# SCH_Auto-tune-FM-reciever_2024-02-23.net
KiCad netlist of a schematic drawn in EasyEDA
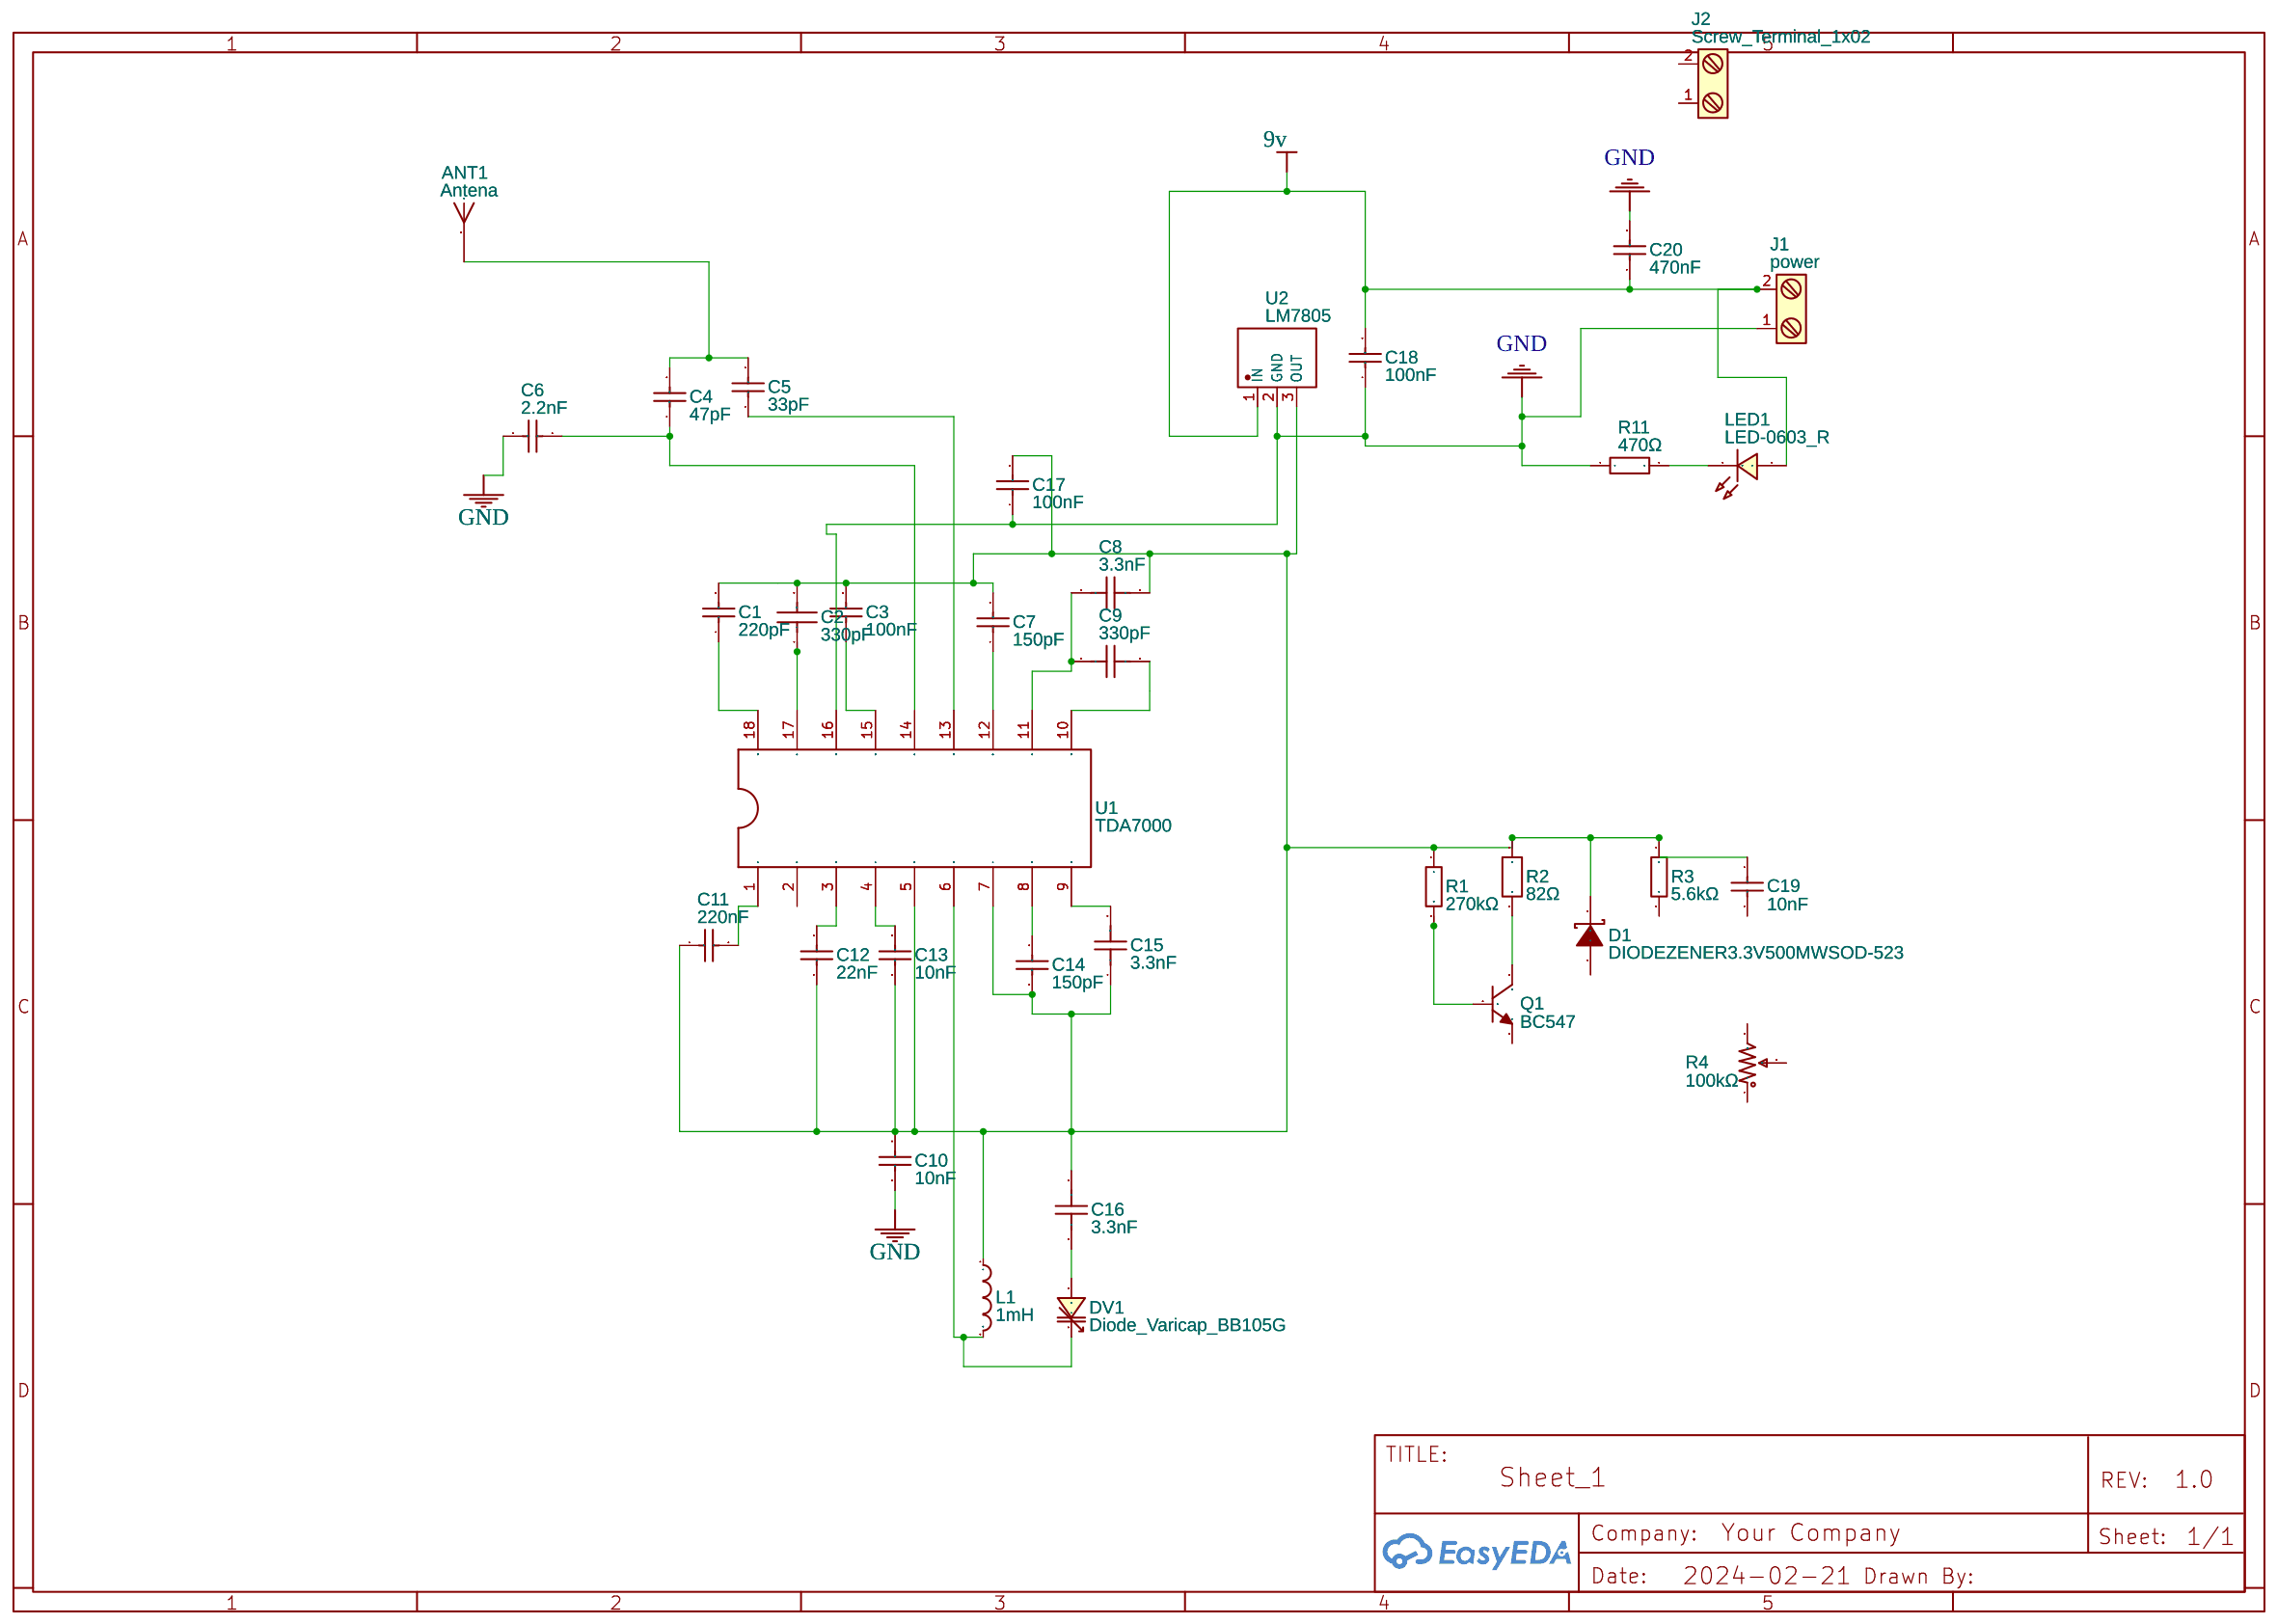
[diagram p0: schematic sheet]

(export (version "E")
  (design (tool "Eeschema 10.0.6"))
  (components
    (comp (ref "ANT1")
      (value "Antena")
      (fields (field (name "Manufacturer Part") "?"))
      (libsource (lib "") (part "Antena"))
    )
    (comp (ref "C1")
      (value "220pF")
      (fields
        (field (name "Manufacturer Part") "CL10B221KB8NNNC")
        (field (name "Manufacturer") "SAMSUNG(三星)")
      )
      (libsource (lib "") (part "CL10B221KB8NNNC"))
    )
    (comp (ref "C2")
      (value "330pF")
      (fields
        (field (name "Manufacturer Part") "CL05C331JB5NNNC")
        (field (name "Manufacturer") "SAMSUNG(三星)")
      )
      (libsource (lib "") (part "CL05C331JB5NNNC"))
    )
    (comp (ref "C3")
      (value "100nF")
      (fields
        (field (name "Manufacturer Part") "CL31B104KBCNNNC")
        (field (name "Manufacturer") "SAMSUNG(三星)")
      )
      (libsource (lib "") (part "CL31B104KBCNNNC"))
    )
    (comp (ref "C4")
      (value "47pF")
      (fields
        (field (name "Manufacturer Part") "CL10C470JB8NNNC")
        (field (name "Manufacturer") "SAMSUNG(三星)")
      )
      (libsource (lib "") (part "CL10C470JB8NNNC"))
    )
    (comp (ref "C5")
      (value "33pF")
      (fields
        (field (name "Manufacturer Part") "CL10C330JB8NNNC")
        (field (name "Manufacturer") "SAMSUNG(三星)")
      )
      (libsource (lib "") (part "CL10C330JB8NNNC"))
    )
    (comp (ref "C6")
      (value "2.2nF")
      (fields
        (field (name "Manufacturer Part") "CL21B222KBANNNC")
        (field (name "Manufacturer") "SAMSUNG(三星)")
      )
      (libsource (lib "") (part "CL21B222KBANNNC"))
    )
    (comp (ref "C7")
      (value "150pF")
      (fields
        (field (name "Manufacturer Part") "CL10C151JB8NNNC")
        (field (name "Manufacturer") "SAMSUNG(三星)")
      )
      (libsource (lib "") (part "CL10C151JB8NNNC"))
    )
    (comp (ref "C8")
      (value "3.3nF")
      (fields
        (field (name "Manufacturer Part") "CL05B332KB5NNNC")
        (field (name "Manufacturer") "SAMSUNG(三星)")
      )
      (libsource (lib "") (part "CL05B332KB5NNNC"))
    )
    (comp (ref "C9")
      (value "330pF")
      (fields
        (field (name "Manufacturer Part") "CL10B331KB8NNNC")
        (field (name "Manufacturer") "SAMSUNG(三星)")
      )
      (libsource (lib "") (part "CL10B331KB8NNNC"))
    )
    (comp (ref "C10")
      (value "10nF")
      (fields
        (field (name "Manufacturer Part") "CL05B103KB5NNNC")
        (field (name "Manufacturer") "SAMSUNG(三星)")
      )
      (libsource (lib "") (part "CL05B103KB5NNNC_1"))
    )
    (comp (ref "C11")
      (value "220nF")
      (fields
        (field (name "Manufacturer Part") "CL21B224KBFNNNE")
        (field (name "Manufacturer") "SAMSUNG(三星)")
      )
      (libsource (lib "") (part "CL21B224KBFNNNE"))
    )
    (comp (ref "C12")
      (value "22nF")
      (fields
        (field (name "Manufacturer Part") "CL21B223KBANNNC")
        (field (name "Manufacturer") "SAMSUNG(三星)")
      )
      (libsource (lib "") (part "CL21B223KBANNNC"))
    )
    (comp (ref "C13")
      (value "10nF")
      (fields
        (field (name "Manufacturer Part") "CL05B103KB5NNNC")
        (field (name "Manufacturer") "SAMSUNG(三星)")
      )
      (libsource (lib "") (part "CL05B103KB5NNNC_1"))
    )
    (comp (ref "C14")
      (value "150pF")
      (fields
        (field (name "Manufacturer Part") "CL10C151JB8NNNC")
        (field (name "Manufacturer") "SAMSUNG(三星)")
      )
      (libsource (lib "") (part "CL10C151JB8NNNC"))
    )
    (comp (ref "C15")
      (value "3.3nF")
      (fields
        (field (name "Manufacturer Part") "CL05B332KB5NNNC")
        (field (name "Manufacturer") "SAMSUNG(三星)")
      )
      (libsource (lib "") (part "CL05B332KB5NNNC_1"))
    )
    (comp (ref "C16")
      (value "3.3nF")
      (fields
        (field (name "Manufacturer Part") "CL05B332KB5NNNC")
        (field (name "Manufacturer") "SAMSUNG(三星)")
      )
      (libsource (lib "") (part "CL05B332KB5NNNC_1"))
    )
    (comp (ref "C17")
      (value "100nF")
      (fields
        (field (name "Manufacturer Part") "CL31B104KBCNNNC")
        (field (name "Manufacturer") "SAMSUNG(三星)")
      )
      (libsource (lib "") (part "CL31B104KBCNNNC"))
    )
    (comp (ref "C18")
      (value "100nF")
      (fields
        (field (name "Manufacturer Part") "CL31B104KBCNNNC")
        (field (name "Manufacturer") "SAMSUNG(三星)")
      )
      (libsource (lib "") (part "CL31B104KBCNNNC"))
    )
    (comp (ref "C19")
      (value "10nF")
      (fields
        (field (name "Manufacturer Part") "CL05B103KB5NNNC")
        (field (name "Manufacturer") "SAMSUNG(三星)")
      )
      (libsource (lib "") (part "CL05B103KB5NNNC"))
    )
    (comp (ref "C20")
      (value "470nF")
      (fields (field (name "Manufacturer Part") "C1608X5R1C474KT000N") (field (name "Manufacturer") "TDK"))
      (libsource (lib "") (part "C1608X5R1C474KT000N"))
    )
    (comp (ref "D1")
      (value "DIODEZENER3.3V500MWSOD-523")
      (libsource (lib "") (part "DIODEZENER3.3V500MWSOD-523"))
    )
    (comp (ref "DV1") (value "Diode_Varicap_BB105G") (libsource (lib "") (part "Diode_Varicap_BB105G")))
    (comp (ref "J1") (value "power") (libsource (lib "") (part "Screw_Terminal_1x02")))
    (comp (ref "J2") (value "Screw_Terminal_1x02") (libsource (lib "") (part "Screw_Terminal_1x02")))
    (comp (ref "L1")
      (value "1mH")
      (fields (field (name "Manufacturer Part") "CKCS4030-1mH/M") (field (name "Manufacturer") "CENKER(岑科)"))
      (libsource (lib "") (part "CKCS4030-1MH/M"))
    )
    (comp (ref "LED1")
      (value "LED-0603_R")
      (fields
        (field (name "Manufacturer Part") "19-217/R6C-AL1M2VY/3T")
        (field (name "Manufacturer") "EVERLIGHT(台湾亿光)")
      )
      (libsource (lib "") (part "LED-0603_R"))
    )
    (comp (ref "Q1")
      (value "BC547")
      (fields (field (name "Manufacturer") "CJ(江苏长电/长晶)"))
      (libsource (lib "") (part "BC547"))
    )
    (comp (ref "R1")
      (value "270kΩ")
      (fields (field (name "Manufacturer Part") "RCT02270KJLF") (field (name "Manufacturer") "HKR"))
      (libsource (lib "") (part "RCT02270KJLF"))
    )
    (comp (ref "R2")
      (value "82Ω")
      (fields (field (name "Manufacturer Part") "CR-06JA7---82R") (field (name "Manufacturer") "Viking(光颉)"))
      (libsource (lib "") (part "CR-06JA7---82R"))
    )
    (comp (ref "R3")
      (value "5.6kΩ")
      (fields (field (name "Manufacturer Part") "MFR-25FTE52-5K6") (field (name "Manufacturer") "YAGEO(国巨)"))
      (libsource (lib "") (part "MFR-25FTE52-5K6"))
    )
    (comp (ref "R4")
      (value "100kΩ")
      (fields (field (name "Manufacturer Part") "CT-94EX104") (field (name "Manufacturer") "NIDEC(尼得科)"))
      (libsource (lib "") (part "CT-94EX104"))
    )
    (comp (ref "R11")
      (value "470Ω")
      (fields (field (name "Manufacturer Part") "RC0402FR-07470RL") (field (name "Manufacturer") "YAGEO(国巨)"))
      (libsource (lib "") (part "RC0402FR-07470RL"))
    )
    (comp (ref "U1") (value "TDA7000") (libsource (lib "") (part "TDA7000")))
    (comp (ref "U2")
      (value "LM7805")
      (fields (field (name "Manufacturer") "TF(拓锋)"))
      (libsource (lib "") (part "LM7805"))
    )
  )
  (nets
    (net (code "1") (name "9v") (class "Default")
      (node (ref "C18") (pin "2") (pinfunction "2_2") (pintype "input"))
      (node (ref "C20") (pin "1") (pinfunction "1_1") (pintype "input"))
      (node (ref "J1") (pin "2") (pintype "unspecified"))
      (node (ref "LED1") (pin "1") (pinfunction "1_1") (pintype "unspecified"))
      (node (ref "U2") (pin "1") (pinfunction "IN_1") (pintype "unspecified"))
    )
    (net (code "2") (name "GND") (class "Default")
      (node (ref "C10") (pin "1") (pinfunction "1_1") (pintype "input"))
      (node (ref "C17") (pin "1") (pinfunction "1_1") (pintype "input"))
      (node (ref "C18") (pin "1") (pinfunction "1_1") (pintype "input"))
      (node (ref "C20") (pin "2") (pinfunction "2_2") (pintype "input"))
      (node (ref "C6") (pin "1") (pinfunction "1_1") (pintype "input"))
      (node (ref "J1") (pin "1") (pintype "unspecified"))
      (node (ref "R11") (pin "1") (pinfunction "1_1") (pintype "input"))
      (node (ref "U1") (pin "16") (pinfunction "16_16") (pintype "unspecified"))
      (node (ref "U2") (pin "2") (pinfunction "GND_2") (pintype "unspecified"))
    )
    (net (code "3") (name "Net-(ANT1-Pad1)") (class "Default")
      (node (ref "ANT1") (pin "1") (pinfunction "1_1") (pintype "unspecified"))
      (node (ref "C4") (pin "2") (pinfunction "2_2") (pintype "input"))
      (node (ref "C5") (pin "2") (pinfunction "2_2") (pintype "input"))
    )
    (net (code "4") (name "Net-(C1-Pad1)") (class "Default")
      (node (ref "C1") (pin "1") (pinfunction "1_1") (pintype "input"))
      (node (ref "U1") (pin "18") (pinfunction "18_18") (pintype "unspecified"))
    )
    (net (code "5") (name "Net-(C2-Pad1)") (class "Default")
      (node (ref "C2") (pin "1") (pinfunction "1_1") (pintype "unspecified"))
      (node (ref "U1") (pin "17") (pinfunction "17_17") (pintype "unspecified"))
    )
    (net (code "6") (name "Net-(C3-Pad1)") (class "Default")
      (node (ref "C3") (pin "1") (pinfunction "1_1") (pintype "input"))
      (node (ref "U1") (pin "15") (pinfunction "15_15") (pintype "unspecified"))
    )
    (net (code "7") (name "Net-(C4-Pad1)") (class "Default")
      (node (ref "C4") (pin "1") (pinfunction "1_1") (pintype "input"))
      (node (ref "C6") (pin "2") (pinfunction "2_2") (pintype "input"))
      (node (ref "U1") (pin "14") (pinfunction "14_14") (pintype "unspecified"))
    )
    (net (code "8") (name "Net-(C5-Pad1)") (class "Default")
      (node (ref "C5") (pin "1") (pinfunction "1_1") (pintype "input"))
      (node (ref "U1") (pin "13") (pinfunction "13_13") (pintype "unspecified"))
    )
    (net (code "9") (name "Net-(C7-Pad1)") (class "Default")
      (node (ref "C7") (pin "1") (pinfunction "1_1") (pintype "input"))
      (node (ref "U1") (pin "12") (pinfunction "12_12") (pintype "unspecified"))
    )
    (net (code "10") (name "Net-(C8-Pad1)") (class "Default")
      (node (ref "C8") (pin "1") (pinfunction "1_1") (pintype "unspecified"))
      (node (ref "C9") (pin "1") (pinfunction "1_1") (pintype "unspecified"))
      (node (ref "U1") (pin "11") (pinfunction "11_11") (pintype "unspecified"))
    )
    (net (code "11") (name "Net-(C9-Pad2)") (class "Default")
      (node (ref "C9") (pin "2") (pinfunction "2_2") (pintype "unspecified"))
      (node (ref "U1") (pin "10") (pinfunction "10_10") (pintype "unspecified"))
    )
    (net (code "12") (name "Net-(C11-Pad2)") (class "Default")
      (node (ref "C11") (pin "2") (pinfunction "2_2") (pintype "input"))
      (node (ref "U1") (pin "1") (pinfunction "1_1") (pintype "unspecified"))
    )
    (net (code "13") (name "Net-(C12-Pad2)") (class "Default")
      (node (ref "C12") (pin "2") (pinfunction "2_2") (pintype "input"))
      (node (ref "U1") (pin "3") (pinfunction "3_3") (pintype "unspecified"))
    )
    (net (code "14") (name "Net-(C13-Pad2)") (class "Default")
      (node (ref "C13") (pin "2") (pinfunction "2_2") (pintype "input"))
      (node (ref "U1") (pin "4") (pinfunction "4_4") (pintype "unspecified"))
    )
    (net (code "15") (name "Net-(C14-Pad2)") (class "Default")
      (node (ref "C14") (pin "2") (pinfunction "2_2") (pintype "input"))
      (node (ref "U1") (pin "8") (pinfunction "8_8") (pintype "unspecified"))
    )
    (net (code "16") (name "Net-(C15-Pad2)") (class "Default")
      (node (ref "C15") (pin "2") (pinfunction "2_2") (pintype "unspecified"))
      (node (ref "U1") (pin "9") (pinfunction "9_9") (pintype "unspecified"))
    )
    (net (code "17") (name "Net-(D1-K)") (class "Default")
      (node (ref "C1") (pin "2") (pinfunction "2_2") (pintype "input"))
      (node (ref "C10") (pin "2") (pinfunction "2_2") (pintype "input"))
      (node (ref "C11") (pin "1") (pinfunction "1_1") (pintype "input"))
      (node (ref "C12") (pin "1") (pinfunction "1_1") (pintype "input"))
      (node (ref "C13") (pin "1") (pinfunction "1_1") (pintype "input"))
      (node (ref "C14") (pin "1") (pinfunction "1_1") (pintype "input"))
      (node (ref "C15") (pin "1") (pinfunction "1_1") (pintype "unspecified"))
      (node (ref "C16") (pin "2") (pinfunction "2_2") (pintype "unspecified"))
      (node (ref "C17") (pin "2") (pinfunction "2_2") (pintype "input"))
      (node (ref "C19") (pin "1") (pinfunction "1_1") (pintype "input"))
      (node (ref "C2") (pin "2") (pinfunction "2_2") (pintype "unspecified"))
      (node (ref "C3") (pin "2") (pinfunction "2_2") (pintype "input"))
      (node (ref "C7") (pin "2") (pinfunction "2_2") (pintype "input"))
      (node (ref "C8") (pin "2") (pinfunction "2_2") (pintype "unspecified"))
      (node (ref "D1") (pin "1") (pinfunction "K_1") (pintype "unspecified"))
      (node (ref "L1") (pin "1") (pinfunction "1_1") (pintype "unspecified"))
      (node (ref "R1") (pin "1") (pinfunction "1_1") (pintype "unspecified"))
      (node (ref "R2") (pin "1") (pinfunction "1_1") (pintype "unspecified"))
      (node (ref "R3") (pin "1") (pinfunction "1_1") (pintype "unspecified"))
      (node (ref "U1") (pin "5") (pinfunction "5_5") (pintype "unspecified"))
      (node (ref "U1") (pin "7") (pinfunction "7_7") (pintype "unspecified"))
      (node (ref "U2") (pin "3") (pinfunction "OUT_3") (pintype "unspecified"))
    )
    (net (code "18") (name "Net-(DV1-A)") (class "Default")
      (node (ref "C16") (pin "1") (pinfunction "1_1") (pintype "unspecified"))
      (node (ref "DV1") (pin "1") (pinfunction "A_1") (pintype "unspecified"))
    )
    (net (code "19") (name "Net-(DV1-K)") (class "Default")
      (node (ref "DV1") (pin "2") (pinfunction "K_2") (pintype "unspecified"))
      (node (ref "L1") (pin "2") (pinfunction "2_2") (pintype "unspecified"))
      (node (ref "U1") (pin "6") (pinfunction "6_6") (pintype "unspecified"))
    )
    (net (code "20") (name "Net-(LED1-Pad2)") (class "Default")
      (node (ref "LED1") (pin "2") (pinfunction "2_2") (pintype "unspecified"))
      (node (ref "R11") (pin "2") (pinfunction "2_2") (pintype "input"))
    )
    (net (code "21") (name "Net-(Q1-B)") (class "Default")
      (node (ref "Q1") (pin "2") (pinfunction "B_2") (pintype "unspecified"))
      (node (ref "R1") (pin "2") (pinfunction "2_2") (pintype "unspecified"))
    )
    (net (code "22") (name "Net-(Q1-C)") (class "Default")
      (node (ref "Q1") (pin "1") (pinfunction "C_1") (pintype "unspecified"))
      (node (ref "R2") (pin "2") (pinfunction "2_2") (pintype "unspecified"))
    )
    (net (code "23") (name "unconnected-(C19-Pad2)") (class "Default")
      (node (ref "C19") (pin "2") (pinfunction "2_2") (pintype "input"))
    )
    (net (code "24") (name "unconnected-(D1-A-Pad2)") (class "Default")
      (node (ref "D1") (pin "2") (pinfunction "A_2") (pintype "unspecified"))
    )
    (net (code "25") (name "unconnected-(J2-Pad1)") (class "Default")
      (node (ref "J2") (pin "1") (pintype "unspecified"))
    )
    (net (code "26") (name "unconnected-(J2-Pad2)") (class "Default")
      (node (ref "J2") (pin "2") (pintype "unspecified"))
    )
    (net (code "27") (name "unconnected-(Q1-E-Pad3)") (class "Default")
      (node (ref "Q1") (pin "3") (pinfunction "E_3") (pintype "unspecified"))
    )
    (net (code "28") (name "unconnected-(R3-Pad2)") (class "Default")
      (node (ref "R3") (pin "2") (pinfunction "2_2") (pintype "unspecified"))
    )
    (net (code "29") (name "unconnected-(R4-Pad1)") (class "Default")
      (node (ref "R4") (pin "1") (pinfunction "1_1") (pintype "unspecified"))
    )
    (net (code "30") (name "unconnected-(R4-Pad2)") (class "Default")
      (node (ref "R4") (pin "2") (pinfunction "2_2") (pintype "unspecified"))
    )
    (net (code "31") (name "unconnected-(R4-Pad3)") (class "Default")
      (node (ref "R4") (pin "3") (pinfunction "3_3") (pintype "unspecified"))
    )
    (net (code "32") (name "unconnected-(U1-Pad2)") (class "Default")
      (node (ref "U1") (pin "2") (pinfunction "2_2") (pintype "unspecified"))
    )
  )
)
